# schematic.net
KiCad netlist of a schematic drawn in EasyEDA
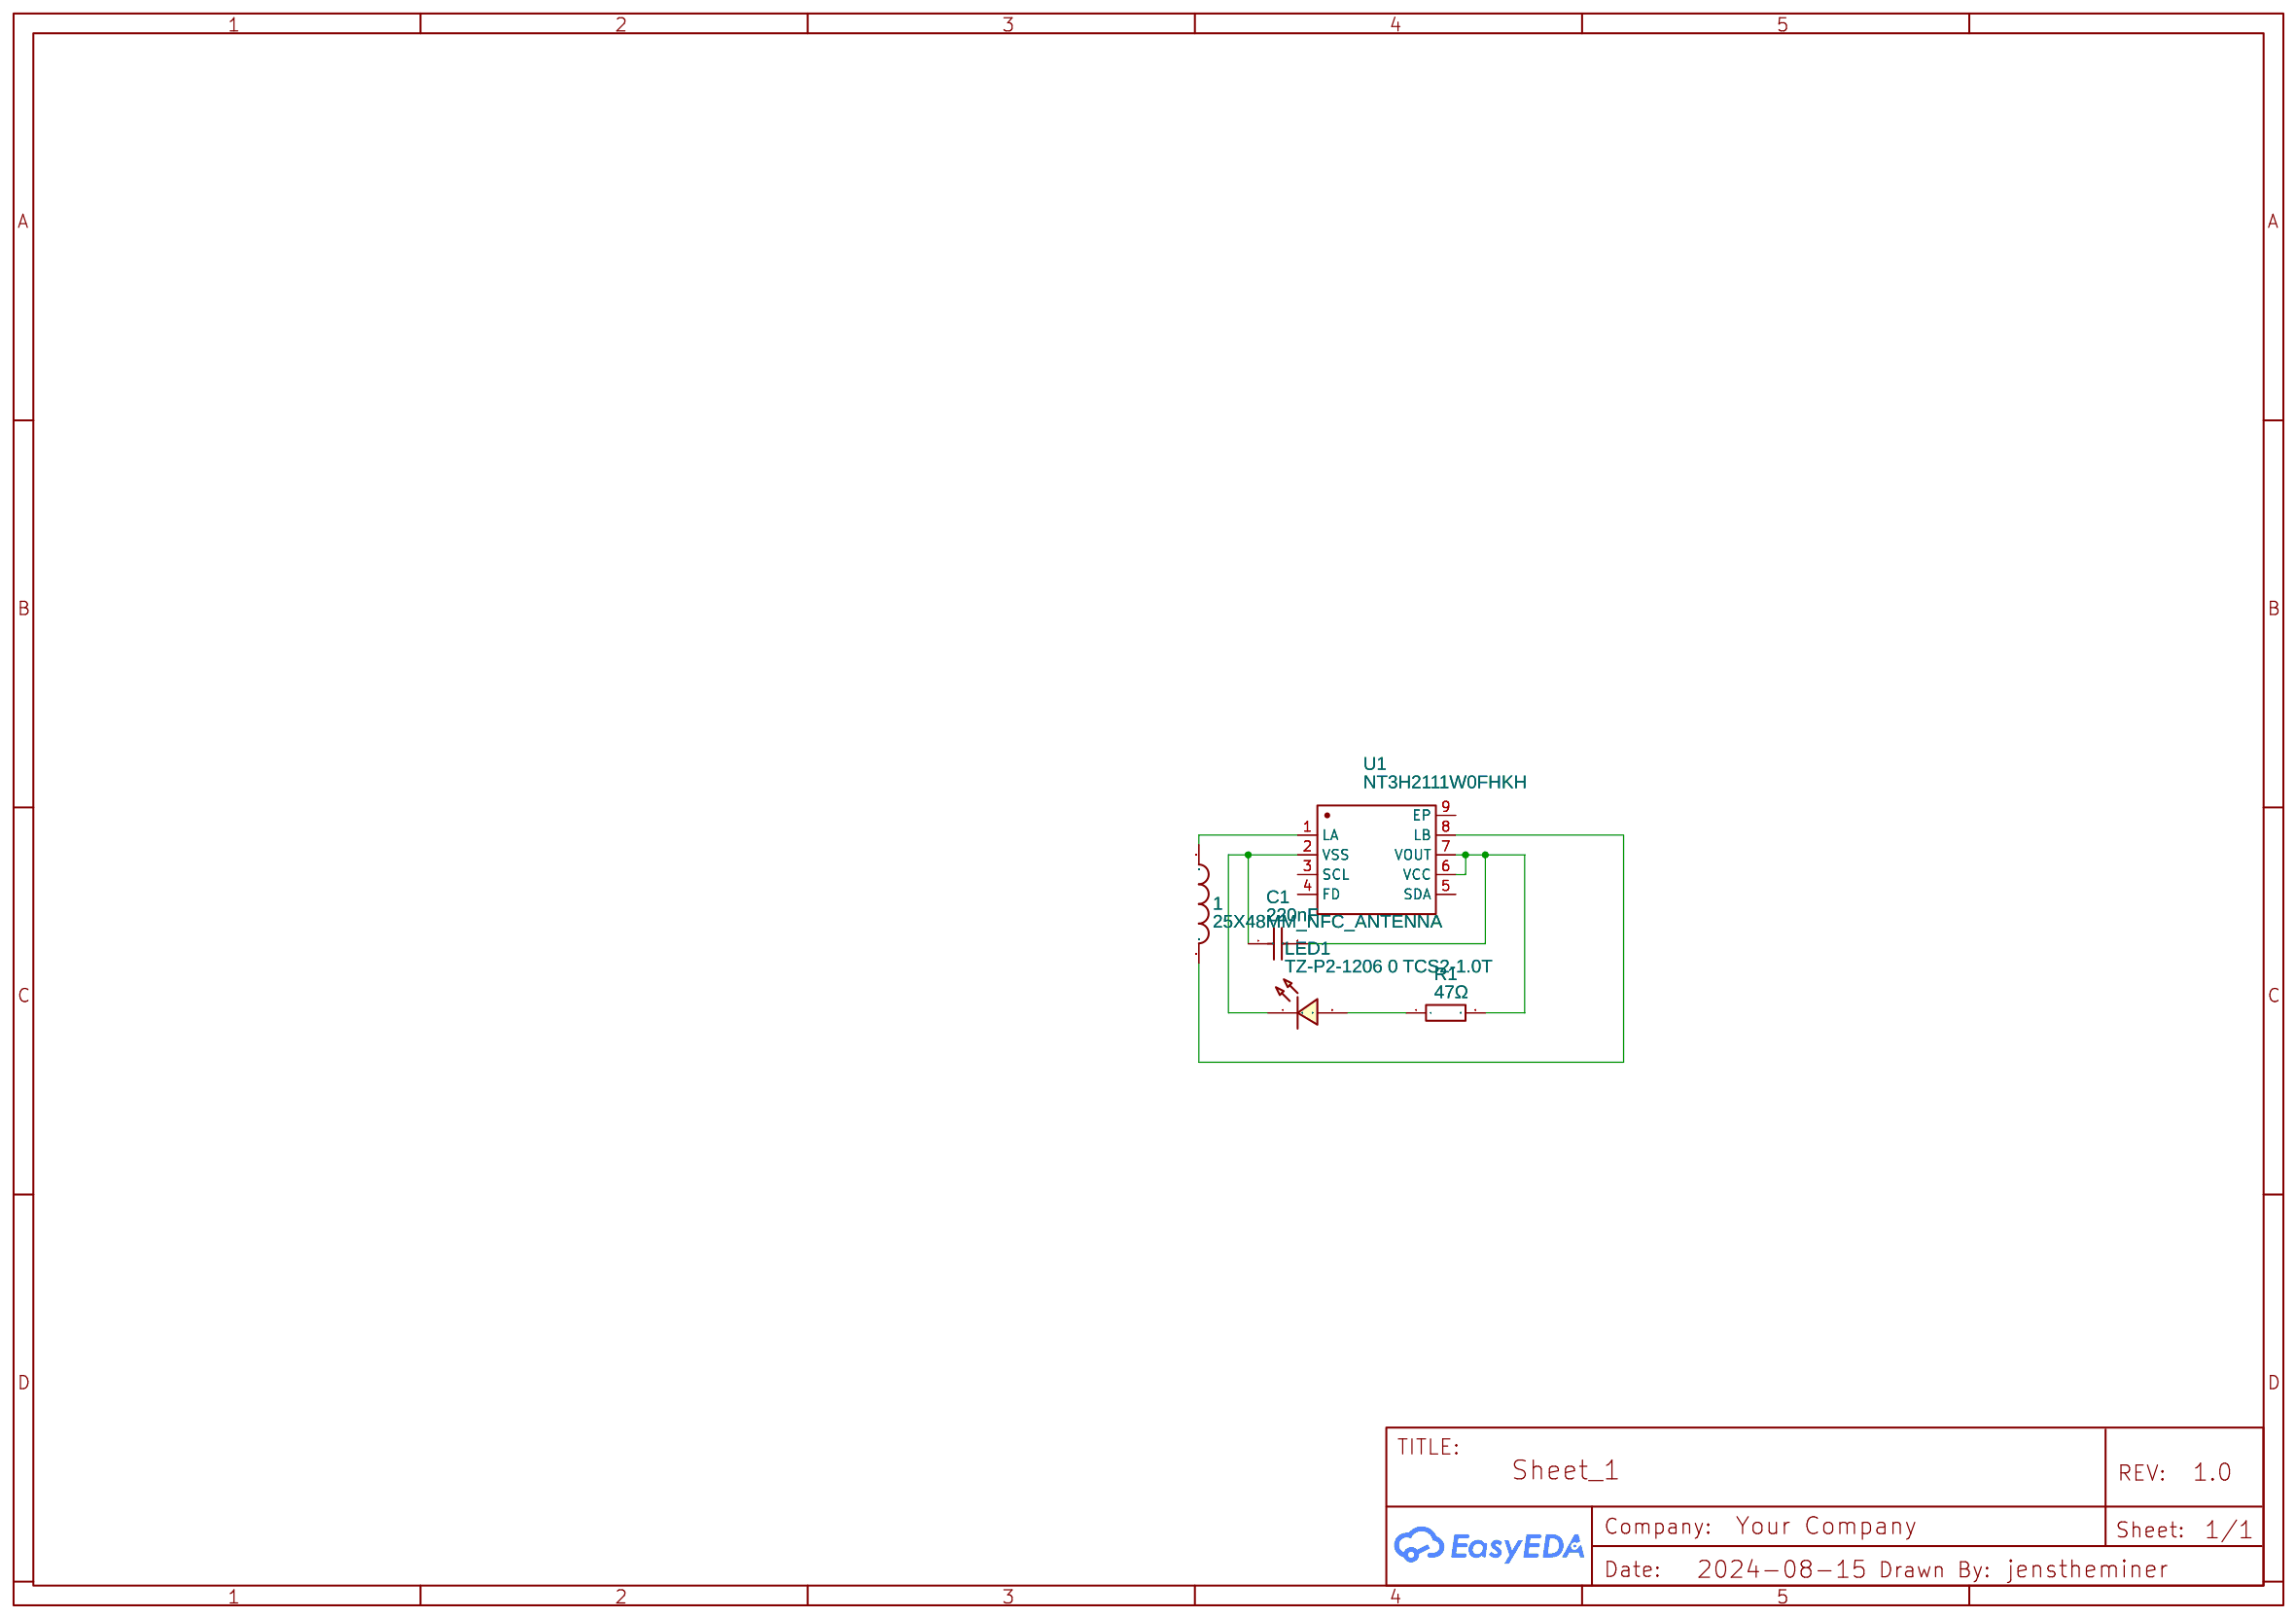
[diagram p0: schematic sheet]

(export (version "E")
  (design (tool "Eeschema 10.0.6"))
  (components
    (comp (ref "1") (value "25X48MM_NFC_ANTENNA") (libsource (lib "") (part "25X48MM_NFC_ANTENNA")))
    (comp (ref "C1")
      (value "220nF")
      (fields
        (field (name "Manufacturer Part") "CL10B224KA8NNNC")
        (field (name "Manufacturer") "SAMSUNG(三星)")
      )
      (libsource (lib "") (part "CL10B224KA8NNNC"))
    )
    (comp (ref "LED1")
      (value "TZ-P2-1206 0 TCS2-1.0T")
      (fields (field (name "Manufacturer") "TUOZHAN(拓展光电)"))
      (libsource (lib "") (part "TZ-P2-1206 0 TCS2-1.0T"))
    )
    (comp (ref "R1")
      (value "47Ω")
      (fields
        (field (name "Manufacturer Part") "0603WAF470JT5E")
        (field (name "Manufacturer") "UNI-ROYAL(厚声)")
      )
      (libsource (lib "") (part "0603WAF470JT5E"))
    )
    (comp (ref "U1")
      (value "NT3H2111W0FHKH")
      (fields (field (name "Manufacturer") "NXP(恩智浦)"))
      (libsource (lib "") (part "NT3H2111W0FHKH"))
    )
  )
  (nets
    (net (code "1") (name "Net-(LED1-Pad2)") (class "Default")
      (node (ref "LED1") (pin "2") (pinfunction "2_2") (pintype "unspecified"))
      (node (ref "R1") (pin "1") (pinfunction "1_1") (pintype "input"))
    )
    (net (code "2") (name "Net-(U1-LA)") (class "Default")
      (node (ref "1") (pin "P$1") (pinfunction "P$1_P$1") (pintype "bidirectional"))
      (node (ref "U1") (pin "1") (pinfunction "LA_1") (pintype "unspecified"))
    )
    (net (code "3") (name "Net-(U1-LB)") (class "Default")
      (node (ref "1") (pin "P$2") (pinfunction "P$2_P$2") (pintype "bidirectional"))
      (node (ref "U1") (pin "8") (pinfunction "LB_8") (pintype "unspecified"))
    )
    (net (code "4") (name "Net-(U1-VCC)") (class "Default")
      (node (ref "C1") (pin "2") (pinfunction "2_2") (pintype "input"))
      (node (ref "R1") (pin "2") (pinfunction "2_2") (pintype "input"))
      (node (ref "U1") (pin "6") (pinfunction "VCC_6") (pintype "unspecified"))
      (node (ref "U1") (pin "7") (pinfunction "VOUT_7") (pintype "unspecified"))
    )
    (net (code "5") (name "Net-(U1-VSS)") (class "Default")
      (node (ref "C1") (pin "1") (pinfunction "1_1") (pintype "input"))
      (node (ref "LED1") (pin "1") (pinfunction "1_1") (pintype "unspecified"))
      (node (ref "U1") (pin "2") (pinfunction "VSS_2") (pintype "unspecified"))
    )
    (net (code "6") (name "unconnected-(U1-EP-Pad9)") (class "Default")
      (node (ref "U1") (pin "9") (pinfunction "EP_9") (pintype "unspecified"))
    )
    (net (code "7") (name "unconnected-(U1-FD-Pad4)") (class "Default")
      (node (ref "U1") (pin "4") (pinfunction "FD_4") (pintype "unspecified"))
    )
    (net (code "8") (name "unconnected-(U1-SCL-Pad3)") (class "Default")
      (node (ref "U1") (pin "3") (pinfunction "SCL_3") (pintype "unspecified"))
    )
    (net (code "9") (name "unconnected-(U1-SDA-Pad5)") (class "Default")
      (node (ref "U1") (pin "5") (pinfunction "SDA_5") (pintype "unspecified"))
    )
  )
)
